# Driver.net
KiCad netlist of a schematic drawn in Altium Designer
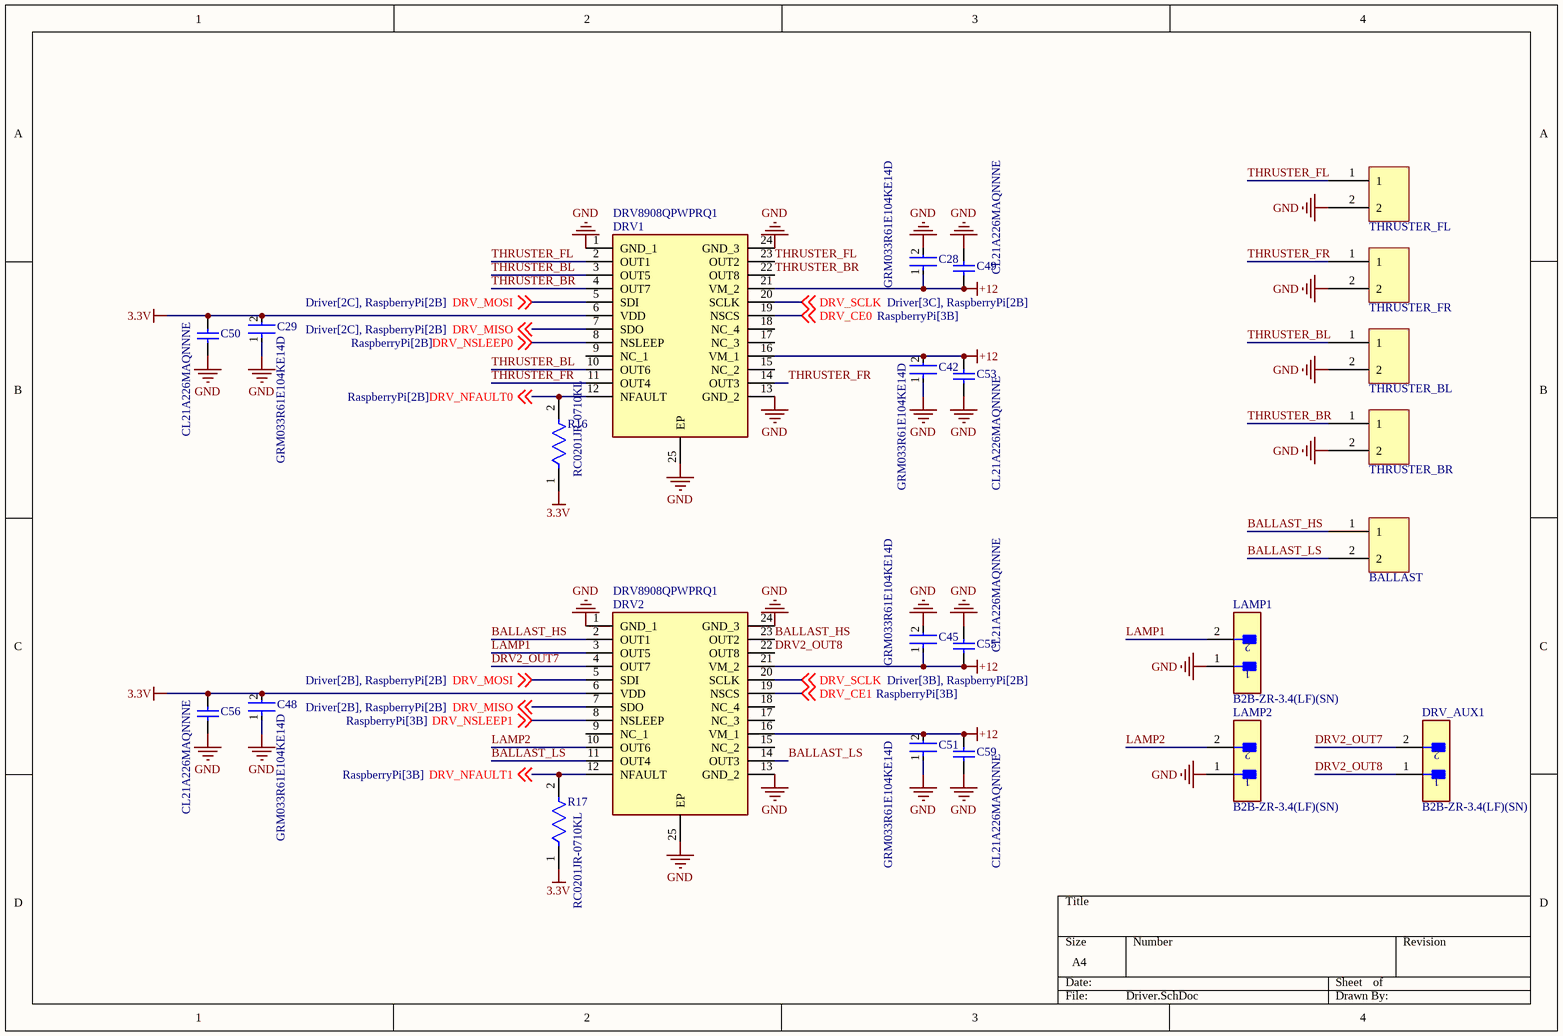
[diagram p0: Driver.SchDoc]

(export (version "E")
  (design (tool "Eeschema 10.0.6"))
  (components
    (comp (ref "BALLAST")
      (value "WJ500V-5.08-2P")
      (footprint "WJ500V-5.08-2P")
      (libsource (lib "WJ500V-5.08-2P") (part "WJ500V-5.08-2P"))
    )
    (comp (ref "C28")
      (value "GRM033R61E104KE14D")
      (footprint "FP-GRM033-0_03-IPC_B")
      (description "Chip Multilayer Ceramic Capacitors for General Purpose, 0201, 0.10uF, X5R, 15%, 10%, 25V")
      (fields (field (name "TOLERANCE") "10%"))
      (libsource (lib "Altium Content Vault") (part "b4654b650e69147ec39a6b967a45e02"))
    )
    (comp (ref "C29")
      (value "GRM033R61E104KE14D")
      (footprint "FP-GRM033-0_03-IPC_B")
      (description "Chip Multilayer Ceramic Capacitors for General Purpose, 0201, 0.10uF, X5R, 15%, 10%, 25V")
      (fields (field (name "TOLERANCE") "10%"))
      (libsource (lib "Altium Content Vault") (part "b4654b650e69147ec39a6b967a45e02"))
    )
    (comp (ref "C42")
      (value "GRM033R61E104KE14D")
      (footprint "FP-GRM033-0_03-IPC_B")
      (description "Chip Multilayer Ceramic Capacitors for General Purpose, 0201, 0.10uF, X5R, 15%, 10%, 25V")
      (fields (field (name "TOLERANCE") "10%"))
      (libsource (lib "Altium Content Vault") (part "b4654b650e69147ec39a6b967a45e02"))
    )
    (comp (ref "C45")
      (value "GRM033R61E104KE14D")
      (footprint "FP-GRM033-0_03-IPC_B")
      (description "Chip Multilayer Ceramic Capacitors for General Purpose, 0201, 0.10uF, X5R, 15%, 10%, 25V")
      (fields (field (name "TOLERANCE") "10%"))
      (libsource (lib "Altium Content Vault") (part "b4654b650e69147ec39a6b967a45e02"))
    )
    (comp (ref "C48")
      (value "GRM033R61E104KE14D")
      (footprint "FP-GRM033-0_03-IPC_B")
      (description "Chip Multilayer Ceramic Capacitors for General Purpose, 0201, 0.10uF, X5R, 15%, 10%, 25V")
      (fields (field (name "TOLERANCE") "10%"))
      (libsource (lib "Altium Content Vault") (part "b4654b650e69147ec39a6b967a45e02"))
    )
    (comp (ref "C49")
      (value "CL21A226MAQNNNE")
      (footprint "CAPC2013X140X45LL15T25")
      (description "Multi-layer Ceramic Capacitor, 22 uF, -55 to 85 degC, 2-Pin SMD (0805), RoHS, Tape and Reel")
      (fields (field (name "MANUFACTURER") "Samsung Electro-Mechanics") (field (name "TOLERANCE") "±20%"))
      (libsource (lib "Altium Content Vault") (part "CAP-NP-2"))
    )
    (comp (ref "C50")
      (value "CL21A226MAQNNNE")
      (footprint "CAPC2013X140X45LL15T25")
      (description "Multi-layer Ceramic Capacitor, 22 uF, -55 to 85 degC, 2-Pin SMD (0805), RoHS, Tape and Reel")
      (fields (field (name "MANUFACTURER") "Samsung Electro-Mechanics") (field (name "TOLERANCE") "±20%"))
      (libsource (lib "Altium Content Vault") (part "CAP-NP-2"))
    )
    (comp (ref "C51")
      (value "GRM033R61E104KE14D")
      (footprint "FP-GRM033-0_03-IPC_B")
      (description "Chip Multilayer Ceramic Capacitors for General Purpose, 0201, 0.10uF, X5R, 15%, 10%, 25V")
      (fields (field (name "TOLERANCE") "10%"))
      (libsource (lib "Altium Content Vault") (part "b4654b650e69147ec39a6b967a45e02"))
    )
    (comp (ref "C53")
      (value "CL21A226MAQNNNE")
      (footprint "CAPC2013X140X45LL15T25")
      (description "Multi-layer Ceramic Capacitor, 22 uF, -55 to 85 degC, 2-Pin SMD (0805), RoHS, Tape and Reel")
      (fields (field (name "MANUFACTURER") "Samsung Electro-Mechanics") (field (name "TOLERANCE") "±20%"))
      (libsource (lib "Altium Content Vault") (part "CAP-NP-2"))
    )
    (comp (ref "C55")
      (value "CL21A226MAQNNNE")
      (footprint "CAPC2013X140X45LL15T25")
      (description "Multi-layer Ceramic Capacitor, 22 uF, -55 to 85 degC, 2-Pin SMD (0805), RoHS, Tape and Reel")
      (fields (field (name "MANUFACTURER") "Samsung Electro-Mechanics") (field (name "TOLERANCE") "±20%"))
      (libsource (lib "Altium Content Vault") (part "CAP-NP-2"))
    )
    (comp (ref "C56")
      (value "CL21A226MAQNNNE")
      (footprint "CAPC2013X140X45LL15T25")
      (description "Multi-layer Ceramic Capacitor, 22 uF, -55 to 85 degC, 2-Pin SMD (0805), RoHS, Tape and Reel")
      (fields (field (name "MANUFACTURER") "Samsung Electro-Mechanics") (field (name "TOLERANCE") "±20%"))
      (libsource (lib "Altium Content Vault") (part "CAP-NP-2"))
    )
    (comp (ref "C59")
      (value "CL21A226MAQNNNE")
      (footprint "CAPC2013X140X45LL15T25")
      (description "Multi-layer Ceramic Capacitor, 22 uF, -55 to 85 degC, 2-Pin SMD (0805), RoHS, Tape and Reel")
      (fields (field (name "MANUFACTURER") "Samsung Electro-Mechanics") (field (name "TOLERANCE") "±20%"))
      (libsource (lib "Altium Content Vault") (part "CAP-NP-2"))
    )
    (comp (ref "DRV1")
      (value "DRV8908QPWPRQ1")
      (footprint "SamacSys:SOP65P640X120-25N")
      (description "Integrated Circuit")
      (fields (field (name "MOUSER PART NUMBER") "595-DRV8908QPWPRQ1"))
      (libsource (lib "*") (part "DRV8908QPWPRQ1"))
    )
    (comp (ref "DRV2")
      (value "DRV8908QPWPRQ1")
      (footprint "SamacSys:SOP65P640X120-25N")
      (description "Integrated Circuit")
      (fields (field (name "MOUSER PART NUMBER") "595-DRV8908QPWPRQ1"))
      (libsource (lib "*") (part "DRV8908QPWPRQ1"))
    )
    (comp (ref "DRV_AUX1")
      (value "B2B-ZR-3.4(LF)(SN)")
      (footprint "FP-B2B-ZR-3_4_LF_SN-MFG")
      (description "CONN HEADER VERT 2POS 1.5MM")
      (libsource (lib "Altium Content Vault") (part "3bc925449376181038e59eaffc5286c"))
    )
    (comp (ref "LAMP1")
      (value "B2B-ZR-3.4(LF)(SN)")
      (footprint "FP-B2B-ZR-3_4_LF_SN-MFG")
      (description "CONN HEADER VERT 2POS 1.5MM")
      (libsource (lib "Altium Content Vault") (part "3bc925449376181038e59eaffc5286c"))
    )
    (comp (ref "LAMP2")
      (value "B2B-ZR-3.4(LF)(SN)")
      (footprint "FP-B2B-ZR-3_4_LF_SN-MFG")
      (description "CONN HEADER VERT 2POS 1.5MM")
      (libsource (lib "Altium Content Vault") (part "3bc925449376181038e59eaffc5286c"))
    )
    (comp (ref "R16")
      (value "RC0201JR-0710KL")
      (footprint "FP-RC0201-0_26-IPC_C")
      (description "RES SMD 10K OHM 5% 1/20W 0201")
      (fields (field (name "TOLERANCE") "5%"))
      (libsource (lib "Altium Content Vault") (part "1029c3af85768c4190bb7ad29bc67b5"))
    )
    (comp (ref "R17")
      (value "RC0201JR-0710KL")
      (footprint "FP-RC0201-0_26-IPC_C")
      (description "RES SMD 10K OHM 5% 1/20W 0201")
      (fields (field (name "TOLERANCE") "5%"))
      (libsource (lib "Altium Content Vault") (part "1029c3af85768c4190bb7ad29bc67b5"))
    )
    (comp (ref "THRUSTER_BL")
      (value "WJ500V-5.08-2P")
      (footprint "WJ500V-5.08-2P")
      (libsource (lib "WJ500V-5.08-2P") (part "WJ500V-5.08-2P"))
    )
    (comp (ref "THRUSTER_BR")
      (value "WJ500V-5.08-2P")
      (footprint "WJ500V-5.08-2P")
      (libsource (lib "WJ500V-5.08-2P") (part "WJ500V-5.08-2P"))
    )
    (comp (ref "THRUSTER_FL")
      (value "WJ500V-5.08-2P")
      (footprint "WJ500V-5.08-2P")
      (libsource (lib "WJ500V-5.08-2P") (part "WJ500V-5.08-2P"))
    )
    (comp (ref "THRUSTER_FR")
      (value "WJ500V-5.08-2P")
      (footprint "WJ500V-5.08-2P")
      (libsource (lib "WJ500V-5.08-2P") (part "WJ500V-5.08-2P"))
    )
  )
  (nets
    (net (code "1") (name "+12") (class "Default")
      (node (ref "C28") (pin "1") (pinfunction "1_1") (pintype "passive"))
      (node (ref "C42") (pin "2") (pinfunction "2_2") (pintype "passive"))
      (node (ref "C45") (pin "1") (pinfunction "1_1") (pintype "passive"))
      (node (ref "C49") (pin "2") (pinfunction "2_2") (pintype "passive"))
      (node (ref "C51") (pin "2") (pinfunction "2_2") (pintype "passive"))
      (node (ref "C53") (pin "2") (pinfunction "2_2") (pintype "passive"))
      (node (ref "C55") (pin "2") (pinfunction "2_2") (pintype "passive"))
      (node (ref "C59") (pin "2") (pinfunction "2_2") (pintype "passive"))
      (node (ref "DRV1") (pin "16") (pinfunction "VM_1_16") (pintype "passive"))
      (node (ref "DRV1") (pin "21") (pinfunction "VM_2_21") (pintype "passive"))
      (node (ref "DRV2") (pin "16") (pinfunction "VM_1_16") (pintype "passive"))
      (node (ref "DRV2") (pin "21") (pinfunction "VM_2_21") (pintype "passive"))
    )
    (net (code "2") (name "/BALLAST_HS") (class "Default")
      (node (ref "BALLAST") (pin "1") (pinfunction "1_1") (pintype "passive"))
      (node (ref "DRV2") (pin "2") (pinfunction "OUT1_2") (pintype "passive"))
      (node (ref "DRV2") (pin "23") (pinfunction "OUT2_23") (pintype "passive"))
    )
    (net (code "3") (name "/BALLAST_LS") (class "Default")
      (node (ref "BALLAST") (pin "2") (pinfunction "2_2") (pintype "passive"))
      (node (ref "DRV2") (pin "11") (pinfunction "OUT4_11") (pintype "passive"))
      (node (ref "DRV2") (pin "14") (pinfunction "OUT3_14") (pintype "passive"))
    )
    (net (code "4") (name "/DRV2_OUT7") (class "Default")
      (node (ref "DRV2") (pin "4") (pinfunction "OUT7_4") (pintype "passive"))
      (node (ref "DRV_AUX1") (pin "2") (pinfunction "2_2") (pintype "passive"))
    )
    (net (code "5") (name "/DRV2_OUT8") (class "Default")
      (node (ref "DRV2") (pin "22") (pinfunction "OUT8_22") (pintype "passive"))
      (node (ref "DRV_AUX1") (pin "1") (pinfunction "1_1") (pintype "passive"))
    )
    (net (code "6") (name "/LAMP1") (class "Default")
      (node (ref "DRV2") (pin "3") (pinfunction "OUT5_3") (pintype "passive"))
      (node (ref "LAMP1") (pin "2") (pinfunction "2_2") (pintype "passive"))
    )
    (net (code "7") (name "/LAMP2") (class "Default")
      (node (ref "DRV2") (pin "10") (pinfunction "OUT6_10") (pintype "passive"))
      (node (ref "LAMP2") (pin "2") (pinfunction "2_2") (pintype "passive"))
    )
    (net (code "8") (name "/THRUSTER_BL") (class "Default")
      (node (ref "DRV1") (pin "10") (pinfunction "OUT6_10") (pintype "passive"))
      (node (ref "DRV1") (pin "3") (pinfunction "OUT5_3") (pintype "passive"))
      (node (ref "THRUSTER_BL") (pin "1") (pinfunction "1_1") (pintype "passive"))
    )
    (net (code "9") (name "/THRUSTER_BR") (class "Default")
      (node (ref "DRV1") (pin "22") (pinfunction "OUT8_22") (pintype "passive"))
      (node (ref "DRV1") (pin "4") (pinfunction "OUT7_4") (pintype "passive"))
      (node (ref "THRUSTER_BR") (pin "1") (pinfunction "1_1") (pintype "passive"))
    )
    (net (code "10") (name "/THRUSTER_FL") (class "Default")
      (node (ref "DRV1") (pin "2") (pinfunction "OUT1_2") (pintype "passive"))
      (node (ref "DRV1") (pin "23") (pinfunction "OUT2_23") (pintype "passive"))
      (node (ref "THRUSTER_FL") (pin "1") (pinfunction "1_1") (pintype "passive"))
    )
    (net (code "11") (name "/THRUSTER_FR") (class "Default")
      (node (ref "DRV1") (pin "11") (pinfunction "OUT4_11") (pintype "passive"))
      (node (ref "DRV1") (pin "14") (pinfunction "OUT3_14") (pintype "passive"))
      (node (ref "THRUSTER_FR") (pin "1") (pinfunction "1_1") (pintype "passive"))
    )
    (net (code "12") (name "3.3V") (class "Default")
      (node (ref "C29") (pin "2") (pinfunction "2_2") (pintype "passive"))
      (node (ref "C48") (pin "2") (pinfunction "2_2") (pintype "passive"))
      (node (ref "C50") (pin "2") (pinfunction "2_2") (pintype "passive"))
      (node (ref "C56") (pin "2") (pinfunction "2_2") (pintype "passive"))
      (node (ref "DRV1") (pin "6") (pinfunction "VDD_6") (pintype "passive"))
      (node (ref "DRV2") (pin "6") (pinfunction "VDD_6") (pintype "passive"))
      (node (ref "R16") (pin "1") (pinfunction "1_1") (pintype "passive"))
      (node (ref "R17") (pin "1") (pinfunction "1_1") (pintype "passive"))
    )
    (net (code "13") (name "DRV_CE0") (class "Default")
      (node (ref "DRV1") (pin "19") (pinfunction "NSCS_19") (pintype "passive"))
    )
    (net (code "14") (name "DRV_CE1") (class "Default")
      (node (ref "DRV2") (pin "19") (pinfunction "NSCS_19") (pintype "passive"))
    )
    (net (code "15") (name "DRV_MISO") (class "Default")
      (node (ref "DRV1") (pin "7") (pinfunction "SDO_7") (pintype "passive"))
      (node (ref "DRV2") (pin "7") (pinfunction "SDO_7") (pintype "passive"))
    )
    (net (code "16") (name "DRV_MOSI") (class "Default")
      (node (ref "DRV1") (pin "5") (pinfunction "SDI_5") (pintype "passive"))
      (node (ref "DRV2") (pin "5") (pinfunction "SDI_5") (pintype "passive"))
    )
    (net (code "17") (name "DRV_NFAULT0") (class "Default")
      (node (ref "DRV1") (pin "12") (pinfunction "NFAULT_12") (pintype "passive"))
      (node (ref "R16") (pin "2") (pinfunction "2_2") (pintype "passive"))
    )
    (net (code "18") (name "DRV_NFAULT1") (class "Default")
      (node (ref "DRV2") (pin "12") (pinfunction "NFAULT_12") (pintype "passive"))
      (node (ref "R17") (pin "2") (pinfunction "2_2") (pintype "passive"))
    )
    (net (code "19") (name "DRV_NSLEEP0") (class "Default")
      (node (ref "DRV1") (pin "8") (pinfunction "NSLEEP_8") (pintype "passive"))
    )
    (net (code "20") (name "DRV_NSLEEP1") (class "Default")
      (node (ref "DRV2") (pin "8") (pinfunction "NSLEEP_8") (pintype "passive"))
    )
    (net (code "21") (name "DRV_SCLK") (class "Default")
      (node (ref "DRV1") (pin "20") (pinfunction "SCLK_20") (pintype "passive"))
      (node (ref "DRV2") (pin "20") (pinfunction "SCLK_20") (pintype "passive"))
    )
    (net (code "22") (name "GND") (class "Default")
      (node (ref "C28") (pin "2") (pinfunction "2_2") (pintype "passive"))
      (node (ref "C29") (pin "1") (pinfunction "1_1") (pintype "passive"))
      (node (ref "C42") (pin "1") (pinfunction "1_1") (pintype "passive"))
      (node (ref "C45") (pin "2") (pinfunction "2_2") (pintype "passive"))
      (node (ref "C48") (pin "1") (pinfunction "1_1") (pintype "passive"))
      (node (ref "C49") (pin "1") (pinfunction "1_1") (pintype "passive"))
      (node (ref "C50") (pin "1") (pinfunction "1_1") (pintype "passive"))
      (node (ref "C51") (pin "1") (pinfunction "1_1") (pintype "passive"))
      (node (ref "C53") (pin "1") (pinfunction "1_1") (pintype "passive"))
      (node (ref "C55") (pin "1") (pinfunction "1_1") (pintype "passive"))
      (node (ref "C56") (pin "1") (pinfunction "1_1") (pintype "passive"))
      (node (ref "C59") (pin "1") (pinfunction "1_1") (pintype "passive"))
      (node (ref "DRV1") (pin "1") (pinfunction "GND_1_1") (pintype "passive"))
      (node (ref "DRV1") (pin "13") (pinfunction "GND_2_13") (pintype "passive"))
      (node (ref "DRV1") (pin "24") (pinfunction "GND_3_24") (pintype "passive"))
      (node (ref "DRV1") (pin "25") (pinfunction "EP_25") (pintype "passive"))
      (node (ref "DRV2") (pin "1") (pinfunction "GND_1_1") (pintype "passive"))
      (node (ref "DRV2") (pin "13") (pinfunction "GND_2_13") (pintype "passive"))
      (node (ref "DRV2") (pin "24") (pinfunction "GND_3_24") (pintype "passive"))
      (node (ref "DRV2") (pin "25") (pinfunction "EP_25") (pintype "passive"))
      (node (ref "LAMP1") (pin "1") (pinfunction "1_1") (pintype "passive"))
      (node (ref "LAMP2") (pin "1") (pinfunction "1_1") (pintype "passive"))
      (node (ref "THRUSTER_BL") (pin "2") (pinfunction "2_2") (pintype "passive"))
      (node (ref "THRUSTER_BR") (pin "2") (pinfunction "2_2") (pintype "passive"))
      (node (ref "THRUSTER_FL") (pin "2") (pinfunction "2_2") (pintype "passive"))
      (node (ref "THRUSTER_FR") (pin "2") (pinfunction "2_2") (pintype "passive"))
    )
    (net (code "23") (name "unconnected-(DRV1-NC_1-Pad9)") (class "Default")
      (node (ref "DRV1") (pin "9") (pinfunction "NC_1_9") (pintype "passive"))
    )
    (net (code "24") (name "unconnected-(DRV1-NC_2-Pad15)") (class "Default")
      (node (ref "DRV1") (pin "15") (pinfunction "NC_2_15") (pintype "passive"))
    )
    (net (code "25") (name "unconnected-(DRV1-NC_3-Pad17)") (class "Default")
      (node (ref "DRV1") (pin "17") (pinfunction "NC_3_17") (pintype "passive"))
    )
    (net (code "26") (name "unconnected-(DRV1-NC_4-Pad18)") (class "Default")
      (node (ref "DRV1") (pin "18") (pinfunction "NC_4_18") (pintype "passive"))
    )
    (net (code "27") (name "unconnected-(DRV2-NC_1-Pad9)") (class "Default")
      (node (ref "DRV2") (pin "9") (pinfunction "NC_1_9") (pintype "passive"))
    )
    (net (code "28") (name "unconnected-(DRV2-NC_2-Pad15)") (class "Default")
      (node (ref "DRV2") (pin "15") (pinfunction "NC_2_15") (pintype "passive"))
    )
    (net (code "29") (name "unconnected-(DRV2-NC_3-Pad17)") (class "Default")
      (node (ref "DRV2") (pin "17") (pinfunction "NC_3_17") (pintype "passive"))
    )
    (net (code "30") (name "unconnected-(DRV2-NC_4-Pad18)") (class "Default")
      (node (ref "DRV2") (pin "18") (pinfunction "NC_4_18") (pintype "passive"))
    )
  )
)
